# EIS_Main_Akku.net
KiCad netlist of a schematic drawn in Altium Designer
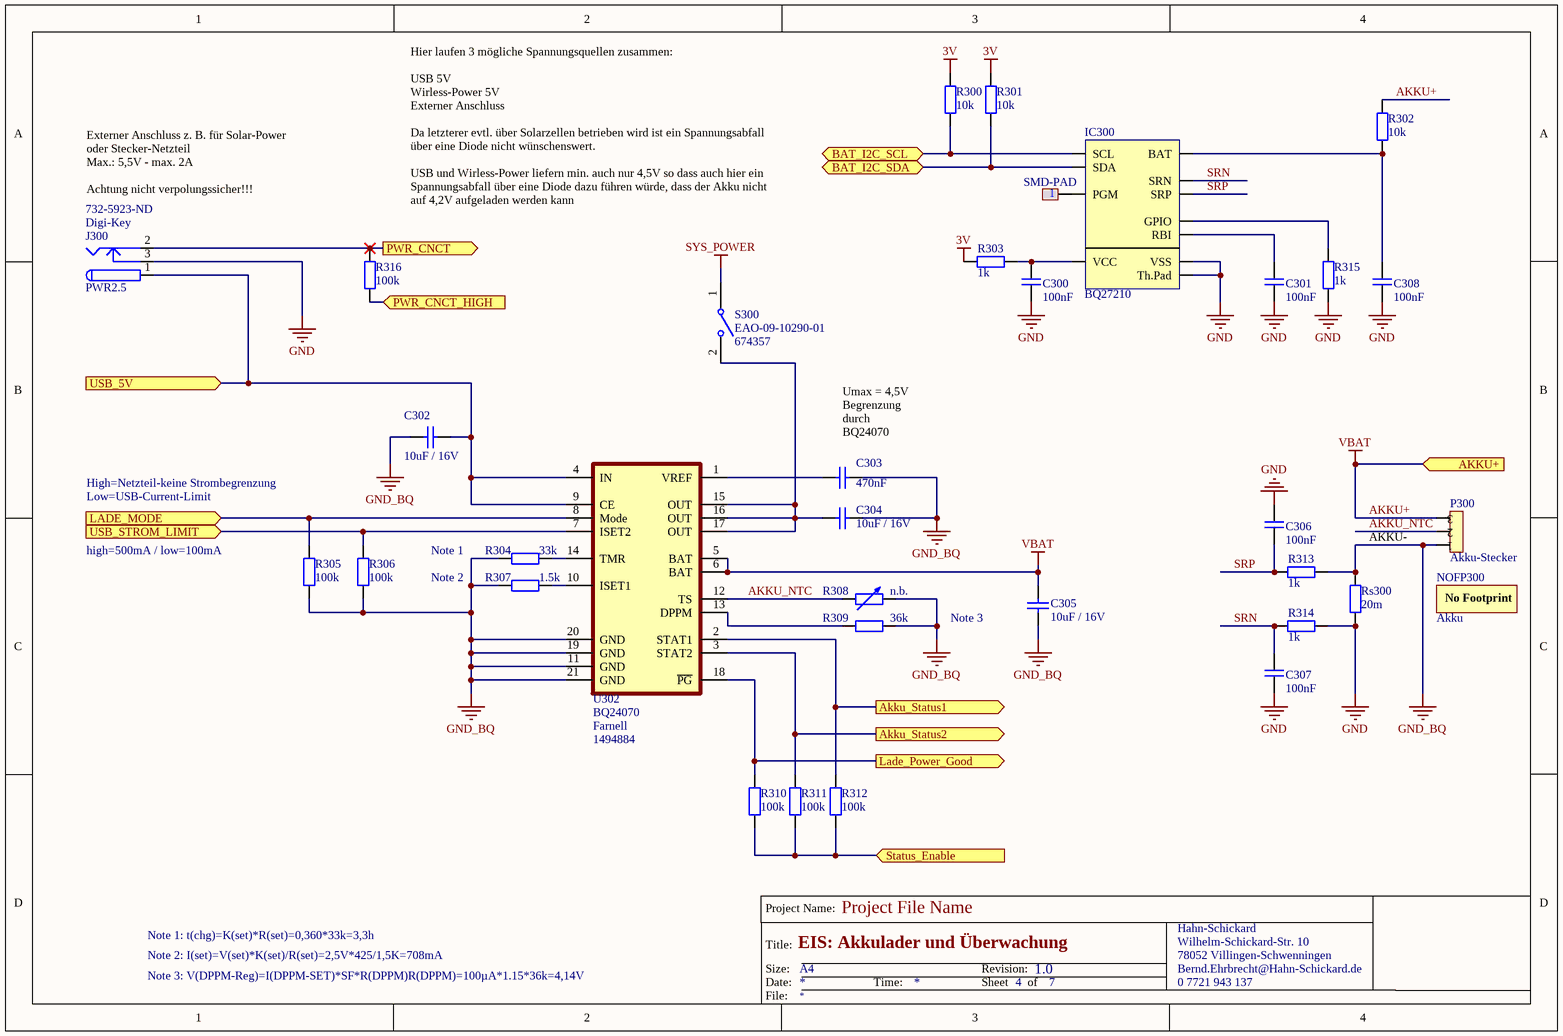
[diagram p0: EIS_Main_Akku.SchDoc]

(export (version "E")
  (design (tool "Eeschema 10.0.6"))
  (components
    (comp (ref "C300")
      (value "100nF")
      (footprint "CAPC1608N")
      (libsource (lib "My_Schlib_6_18") (part "Kondensator SMD Keramik"))
    )
    (comp (ref "C301")
      (value "100nF")
      (footprint "CAPC1608N")
      (libsource (lib "My_Schlib_6_18") (part "Kondensator SMD Keramik"))
    )
    (comp (ref "C302")
      (value "10uF / 16V")
      (footprint "CAPC2012N")
      (description "Ceramic Chip Capacitor - Standard")
      (fields (field (name "PUBLISHER") "Altium Limited"))
      (libsource (lib "KEMET Chip Capacitor") (part "C0805"))
    )
    (comp (ref "C303")
      (value "470nF")
      (footprint "CAPC1608N")
      (description "Ceramic Chip Capacitor - Standard")
      (fields (field (name "PUBLISHER") "Altium Limited"))
      (libsource (lib "KEMET Chip Capacitor") (part "C0805"))
    )
    (comp (ref "C304")
      (value "10uF / 16V")
      (footprint "CAPC2012N")
      (description "Ceramic Chip Capacitor - Standard")
      (fields (field (name "PUBLISHER") "Altium Limited"))
      (libsource (lib "KEMET Chip Capacitor") (part "C0805"))
    )
    (comp (ref "C305")
      (value "10uF / 16V")
      (footprint "CAPC2012N")
      (description "Ceramic Chip Capacitor - Standard")
      (fields (field (name "PUBLISHER") "Altium Limited"))
      (libsource (lib "KEMET Chip Capacitor") (part "C0805"))
    )
    (comp (ref "C306")
      (value "100nF")
      (footprint "CAPC1608N")
      (libsource (lib "My_Schlib_6_18") (part "Kondensator SMD Keramik"))
    )
    (comp (ref "C307")
      (value "100nF")
      (footprint "CAPC1608N")
      (libsource (lib "My_Schlib_6_18") (part "Kondensator SMD Keramik"))
    )
    (comp (ref "C308")
      (value "100nF")
      (footprint "CAPC1608N")
      (libsource (lib "My_Schlib_6_18") (part "Kondensator SMD Keramik"))
    )
    (comp (ref "IC300")
      (value "BQ27210")
      (footprint "TI-DRK-PVSON")
      (description "i-Ion AND Li-Pol BATTERY GAS GAUGE IC FOR PORTABLE APPLICATIONS")
      (fields (field (name "10_ERSTELL_DATUM") "DD.MM.YYYY") (field (name "09_ERSTELLER") "HSG Name"))
      (libsource (lib "Eis_Lib") (part "BQ27210"))
    )
    (comp (ref "J300")
      (value "PWR2.5")
      (footprint "WE_694102304002")
      (description "Low Voltage Power Supply Connector")
      (fields
        (field (name "SUPPLIER 1") "Digi-Key")
        (field (name "SUPPLIER PART NUMBER 1") "732-5923-ND")
        (field (name "PUBLISHER") "Altium Limited")
      )
      (libsource (lib "Miscellaneous Connectors") (part "PWR2.5"))
    )
    (comp (ref "NOFP300")
      (value "Akku")
      (footprint "No_Footprint")
      (description "Dummy-Bauteil, um Zusatzbestellungen in die BOM einzutragen")
      (fields (field (name "Comment") "No-Footprint"))
      (libsource (lib "RudiSchlibAllg") (part "No-Footprint"))
    )
    (comp (ref "P300")
      (value "Akku-Stecker")
      (footprint "S3B-XH-A")
      (description "Header, 3-Pin")
      (fields (field (name "PUBLISHER") "Altium Limited"))
      (libsource (lib "RudiSchlibAllg") (part "Header 3X1"))
    )
    (comp (ref "R300")
      (value "10k")
      (footprint "RESC1608N")
      (description "Resistor")
      (fields (field (name "PUBLISHER") "Altium Limited"))
      (libsource (lib "Miscellaneous Devices") (part "Res2"))
    )
    (comp (ref "R301")
      (value "10k")
      (footprint "RESC1608N")
      (description "Resistor")
      (fields (field (name "PUBLISHER") "Altium Limited"))
      (libsource (lib "Miscellaneous Devices") (part "Res2"))
    )
    (comp (ref "R302")
      (value "10k")
      (footprint "RESC1608N")
      (description "Resistor")
      (fields (field (name "PUBLISHER") "Altium Limited"))
      (libsource (lib "Miscellaneous Devices") (part "Res2"))
    )
    (comp (ref "R303")
      (value "1k")
      (footprint "RESC1608N")
      (description "Resistor")
      (fields (field (name "PUBLISHER") "Altium Limited"))
      (libsource (lib "") (part "Res2_2"))
    )
    (comp (ref "R304")
      (value "33k")
      (footprint "RESC1608N")
      (description "Resistor")
      (fields (field (name "PUBLISHER") "Altium Limited"))
      (libsource (lib "") (part "Res2_3"))
    )
    (comp (ref "R305")
      (value "100k")
      (footprint "RESC1608N")
      (description "Resistor")
      (fields (field (name "PUBLISHER") "Altium Limited"))
      (libsource (lib "Miscellaneous Devices") (part "Res2"))
    )
    (comp (ref "R306")
      (value "100k")
      (footprint "RESC1608N")
      (description "Resistor")
      (fields (field (name "PUBLISHER") "Altium Limited"))
      (libsource (lib "Miscellaneous Devices") (part "Res2"))
    )
    (comp (ref "R307")
      (value "1.5k")
      (footprint "RESC1608N")
      (description "Resistor")
      (fields (field (name "PUBLISHER") "Altium Limited"))
      (libsource (lib "") (part "Res2_3"))
    )
    (comp (ref "R308")
      (value "n.b.")
      (footprint "RESC1608N")
      (description "Variable Resistor")
      (fields (field (name "PUBLISHER") "Altium Limited"))
      (libsource (lib "Miscellaneous Devices") (part "Res Adj2"))
    )
    (comp (ref "R309")
      (value "36k")
      (footprint "RESC1608N")
      (description "Resistor")
      (fields (field (name "PUBLISHER") "Altium Limited"))
      (libsource (lib "") (part "Res2_3"))
    )
    (comp (ref "R310")
      (value "100k")
      (footprint "RESC1608N")
      (description "Resistor")
      (fields (field (name "PUBLISHER") "Altium Limited"))
      (libsource (lib "Miscellaneous Devices") (part "Res2"))
    )
    (comp (ref "R311")
      (value "100k")
      (footprint "RESC1608N")
      (description "Resistor")
      (fields (field (name "PUBLISHER") "Altium Limited"))
      (libsource (lib "Miscellaneous Devices") (part "Res2"))
    )
    (comp (ref "R312")
      (value "100k")
      (footprint "RESC1608N")
      (description "Resistor")
      (fields (field (name "PUBLISHER") "Altium Limited"))
      (libsource (lib "Miscellaneous Devices") (part "Res2"))
    )
    (comp (ref "R313")
      (value "1k")
      (footprint "RESC1608N")
      (description "Resistor")
      (fields (field (name "PUBLISHER") "Altium Limited"))
      (libsource (lib "") (part "Res2_2"))
    )
    (comp (ref "R314")
      (value "1k")
      (footprint "RESC1608N")
      (description "Resistor")
      (fields (field (name "PUBLISHER") "Altium Limited"))
      (libsource (lib "") (part "Res2_2"))
    )
    (comp (ref "R315")
      (value "1k")
      (footprint "RESC1608N")
      (description "Resistor")
      (fields (field (name "PUBLISHER") "Altium Limited"))
      (libsource (lib "") (part "Res2_1"))
    )
    (comp (ref "R316")
      (value "100k")
      (footprint "RESC1608N")
      (description "Resistor")
      (fields (field (name "PUBLISHER") "Altium Limited"))
      (libsource (lib "Miscellaneous Devices") (part "Res2"))
    )
    (comp (ref "Rs300")
      (value "20m")
      (footprint "RESC3216N")
      (description "RESC1005N (R0402)")
      (fields (field (name "PUBLISHER") "HSG Jürgen Merz"))
      (libsource (lib "HSG-IMIT_JuergenMerz") (part "RESC1005N (R0402)"))
    )
    (comp (ref "S300")
      (value "EAO-09-10290-01")
      (footprint "EAO09-10290-01")
      (description "Schalter universal 1Polig")
      (fields
        (field (name "SUPPLIER PART NUMBER 1") "674357")
        (field (name "10_ERSTELL_DATUM") "DD-MM-YYYY")
        (field (name "09_ERSTELLER") "HSG Name")
      )
      (libsource (lib "MetaSensClampOn_BT") (part "Schalter universal 1Polig"))
    )
    (comp (ref "S301")
      (value "SMD-PAD")
      (footprint "SMD_PAD")
      (description "SMD-PAD für Debugvorgang")
      (libsource (lib "RudiSchlibAllg") (part "SMD_PAD"))
    )
    (comp (ref "U302")
      (value "BQ24070")
      (footprint "R-PVQFN50P450X350X100-20N")
      (description "Lithum Ion Ladebaustein, Power Path")
      (fields (field (name "SUPPLIER 1") "Farnell") (field (name "SUPPLIER PART NUMBER 1") "1494884"))
      (libsource (lib "Mekka") (part "BQ24070"))
    )
  )
  (nets
    (net (code "1") (name "/AKKU_NTC") (class "Default")
      (node (ref "P300") (pin "2") (pinfunction "2_2") (pintype "passive"))
      (node (ref "R308") (pin "1") (pinfunction "1_1") (pintype "passive"))
      (node (ref "U302") (pin "12") (pinfunction "TS_12") (pintype "passive"))
    )
    (net (code "2") (name "/Akku_Status1") (class "Default")
      (node (ref "R312") (pin "2") (pinfunction "2_2") (pintype "passive"))
      (node (ref "U302") (pin "2") (pinfunction "STAT1_2") (pintype "open_collector"))
    )
    (net (code "3") (name "/Akku_Status2") (class "Default")
      (node (ref "R311") (pin "2") (pinfunction "2_2") (pintype "passive"))
      (node (ref "U302") (pin "3") (pinfunction "STAT2_3") (pintype "open_collector"))
    )
    (net (code "4") (name "/BAT_I2C_SCL") (class "Default")
      (node (ref "IC300") (pin "4") (pinfunction "SCL_4") (pintype "passive"))
      (node (ref "R300") (pin "1") (pinfunction "1_1") (pintype "passive"))
    )
    (net (code "5") (name "/BAT_I2C_SDA") (class "Default")
      (node (ref "IC300") (pin "5") (pinfunction "SDA_5") (pintype "passive"))
      (node (ref "R301") (pin "1") (pinfunction "1_1") (pintype "passive"))
    )
    (net (code "6") (name "/LADE_MODE") (class "Default")
      (node (ref "R305") (pin "2") (pinfunction "2_2") (pintype "passive"))
      (node (ref "U302") (pin "8") (pinfunction "Mode_8") (pintype "passive"))
    )
    (net (code "7") (name "/Lade_Power_Good") (class "Default")
      (node (ref "R310") (pin "2") (pinfunction "2_2") (pintype "passive"))
      (node (ref "U302") (pin "18") (pinfunction "~{PG}_18") (pintype "open_emitter"))
    )
    (net (code "8") (name "/PWR_CNCT") (class "Default")
      (node (ref "J300") (pin "2") (pinfunction "2_2") (pintype "power_in"))
      (node (ref "R316") (pin "2") (pinfunction "2_2") (pintype "passive"))
    )
    (net (code "9") (name "/PWR_CNCT_HIGH") (class "Default")
      (node (ref "R316") (pin "1") (pinfunction "1_1") (pintype "passive"))
    )
    (net (code "10") (name "/SRN") (class "Default")
      (node (ref "C307") (pin "2") (pinfunction "2_2") (pintype "passive"))
      (node (ref "IC300") (pin "7") (pinfunction "SRN_7") (pintype "passive"))
      (node (ref "R314") (pin "2") (pinfunction "2_2") (pintype "passive"))
    )
    (net (code "11") (name "/SRP") (class "Default")
      (node (ref "C306") (pin "2") (pinfunction "2_2") (pintype "passive"))
      (node (ref "IC300") (pin "8") (pinfunction "SRP_8") (pintype "passive"))
      (node (ref "R313") (pin "2") (pinfunction "2_2") (pintype "passive"))
    )
    (net (code "12") (name "/Status_Enable") (class "Default")
      (node (ref "R310") (pin "1") (pinfunction "1_1") (pintype "passive"))
      (node (ref "R311") (pin "1") (pinfunction "1_1") (pintype "passive"))
      (node (ref "R312") (pin "1") (pinfunction "1_1") (pintype "passive"))
    )
    (net (code "13") (name "/USB_5V") (class "Default")
      (node (ref "C302") (pin "2") (pinfunction "2_2") (pintype "passive"))
      (node (ref "J300") (pin "1") (pinfunction "1_1") (pintype "passive"))
      (node (ref "U302") (pin "4") (pinfunction "IN_4") (pintype "passive"))
      (node (ref "U302") (pin "9") (pinfunction "CE_9") (pintype "passive"))
    )
    (net (code "14") (name "/USB_STROM_LIMIT") (class "Default")
      (node (ref "R306") (pin "2") (pinfunction "2_2") (pintype "passive"))
      (node (ref "U302") (pin "7") (pinfunction "ISET2_7") (pintype "passive"))
    )
    (net (code "15") (name "3V") (class "Default")
      (node (ref "R300") (pin "2") (pinfunction "2_2") (pintype "passive"))
      (node (ref "R301") (pin "2") (pinfunction "2_2") (pintype "passive"))
      (node (ref "R303") (pin "2") (pinfunction "2_2") (pintype "passive"))
    )
    (net (code "16") (name "GND") (class "Default")
      (node (ref "C300") (pin "1") (pinfunction "1_1") (pintype "passive"))
      (node (ref "C301") (pin "1") (pinfunction "1_1") (pintype "passive"))
      (node (ref "C306") (pin "1") (pinfunction "1_1") (pintype "passive"))
      (node (ref "C307") (pin "1") (pinfunction "1_1") (pintype "passive"))
      (node (ref "C308") (pin "1") (pinfunction "1_1") (pintype "passive"))
      (node (ref "IC300") (pin "11") (pinfunction "Th.Pad_11") (pintype "power_in"))
      (node (ref "IC300") (pin "3") (pinfunction "VSS_3") (pintype "power_in"))
      (node (ref "J300") (pin "3") (pinfunction "3_3") (pintype "power_in"))
      (node (ref "R314") (pin "1") (pinfunction "1_1") (pintype "passive"))
      (node (ref "R315") (pin "2") (pinfunction "2_2") (pintype "passive"))
      (node (ref "Rs300") (pin "1") (pinfunction "1_1") (pintype "passive"))
    )
    (net (code "17") (name "GND_BQ") (class "Default")
      (node (ref "C302") (pin "1") (pinfunction "1_1") (pintype "passive"))
      (node (ref "C303") (pin "2") (pinfunction "2_2") (pintype "passive"))
      (node (ref "C304") (pin "2") (pinfunction "2_2") (pintype "passive"))
      (node (ref "C305") (pin "1") (pinfunction "1_1") (pintype "passive"))
      (node (ref "P300") (pin "1") (pinfunction "1_1") (pintype "passive"))
      (node (ref "R304") (pin "1") (pinfunction "1_1") (pintype "passive"))
      (node (ref "R305") (pin "1") (pinfunction "1_1") (pintype "passive"))
      (node (ref "R306") (pin "1") (pinfunction "1_1") (pintype "passive"))
      (node (ref "R307") (pin "1") (pinfunction "1_1") (pintype "passive"))
      (node (ref "R308") (pin "2") (pinfunction "2_2") (pintype "passive"))
      (node (ref "R309") (pin "2") (pinfunction "2_2") (pintype "passive"))
      (node (ref "R313") (pin "1") (pinfunction "1_1") (pintype "passive"))
      (node (ref "Rs300") (pin "2") (pinfunction "2_2") (pintype "passive"))
      (node (ref "U302") (pin "11") (pinfunction "GND_11") (pintype "passive"))
      (node (ref "U302") (pin "19") (pinfunction "GND_19") (pintype "passive"))
      (node (ref "U302") (pin "20") (pinfunction "GND_20") (pintype "passive"))
      (node (ref "U302") (pin "21") (pinfunction "GND_21") (pintype "passive"))
    )
    (net (code "18") (name "Net-(IC300-BAT)") (class "Default")
      (node (ref "C308") (pin "2") (pinfunction "2_2") (pintype "passive"))
      (node (ref "IC300") (pin "6") (pinfunction "BAT_6") (pintype "passive"))
      (node (ref "R302") (pin "1") (pinfunction "1_1") (pintype "passive"))
    )
    (net (code "19") (name "Net-(IC300-GPIO)") (class "Default")
      (node (ref "IC300") (pin "9") (pinfunction "GPIO_9") (pintype "passive"))
      (node (ref "R315") (pin "1") (pinfunction "1_1") (pintype "passive"))
    )
    (net (code "20") (name "Net-(IC300-PGM)") (class "Default")
      (node (ref "IC300") (pin "10") (pinfunction "PGM_10") (pintype "passive"))
      (node (ref "S301") (pin "1") (pinfunction "1_1") (pintype "passive"))
    )
    (net (code "21") (name "Net-(IC300-RBI)") (class "Default")
      (node (ref "C301") (pin "2") (pinfunction "2_2") (pintype "passive"))
      (node (ref "IC300") (pin "1") (pinfunction "RBI_1") (pintype "passive"))
    )
    (net (code "22") (name "Net-(IC300-VCC)") (class "Default")
      (node (ref "C300") (pin "2") (pinfunction "2_2") (pintype "passive"))
      (node (ref "IC300") (pin "2") (pinfunction "VCC_2") (pintype "power_in"))
      (node (ref "R303") (pin "1") (pinfunction "1_1") (pintype "passive"))
    )
    (net (code "23") (name "Net-(S300-NO)") (class "Default")
      (node (ref "C304") (pin "1") (pinfunction "1_1") (pintype "passive"))
      (node (ref "S300") (pin "2") (pinfunction "NO_2") (pintype "passive"))
      (node (ref "U302") (pin "15") (pinfunction "OUT_15") (pintype "passive"))
      (node (ref "U302") (pin "16") (pinfunction "OUT_16") (pintype "passive"))
      (node (ref "U302") (pin "17") (pinfunction "OUT_17") (pintype "passive"))
    )
    (net (code "24") (name "Net-(U302-DPPM)") (class "Default")
      (node (ref "R309") (pin "1") (pinfunction "1_1") (pintype "passive"))
      (node (ref "U302") (pin "13") (pinfunction "DPPM_13") (pintype "passive"))
    )
    (net (code "25") (name "Net-(U302-ISET1)") (class "Default")
      (node (ref "R307") (pin "2") (pinfunction "2_2") (pintype "passive"))
      (node (ref "U302") (pin "10") (pinfunction "ISET1_10") (pintype "passive"))
    )
    (net (code "26") (name "Net-(U302-TMR)") (class "Default")
      (node (ref "R304") (pin "2") (pinfunction "2_2") (pintype "passive"))
      (node (ref "U302") (pin "14") (pinfunction "TMR_14") (pintype "passive"))
    )
    (net (code "27") (name "Net-(U302-VREF)") (class "Default")
      (node (ref "C303") (pin "1") (pinfunction "1_1") (pintype "passive"))
      (node (ref "U302") (pin "1") (pinfunction "VREF_1") (pintype "passive"))
    )
    (net (code "28") (name "SYS_POWER") (class "Default")
      (node (ref "S300") (pin "1") (pinfunction "COMMON_1") (pintype "passive"))
    )
    (net (code "29") (name "VBAT") (class "Default")
      (node (ref "C305") (pin "2") (pinfunction "2_2") (pintype "passive"))
      (node (ref "P300") (pin "3") (pinfunction "3_3") (pintype "passive"))
      (node (ref "R302") (pin "2") (pinfunction "2_2") (pintype "passive"))
      (node (ref "U302") (pin "5") (pinfunction "BAT_5") (pintype "passive"))
      (node (ref "U302") (pin "6") (pinfunction "BAT_6") (pintype "passive"))
    )
  )
)
